# DCDC_Jetson.net
KiCad netlist of a schematic drawn in Altium Designer
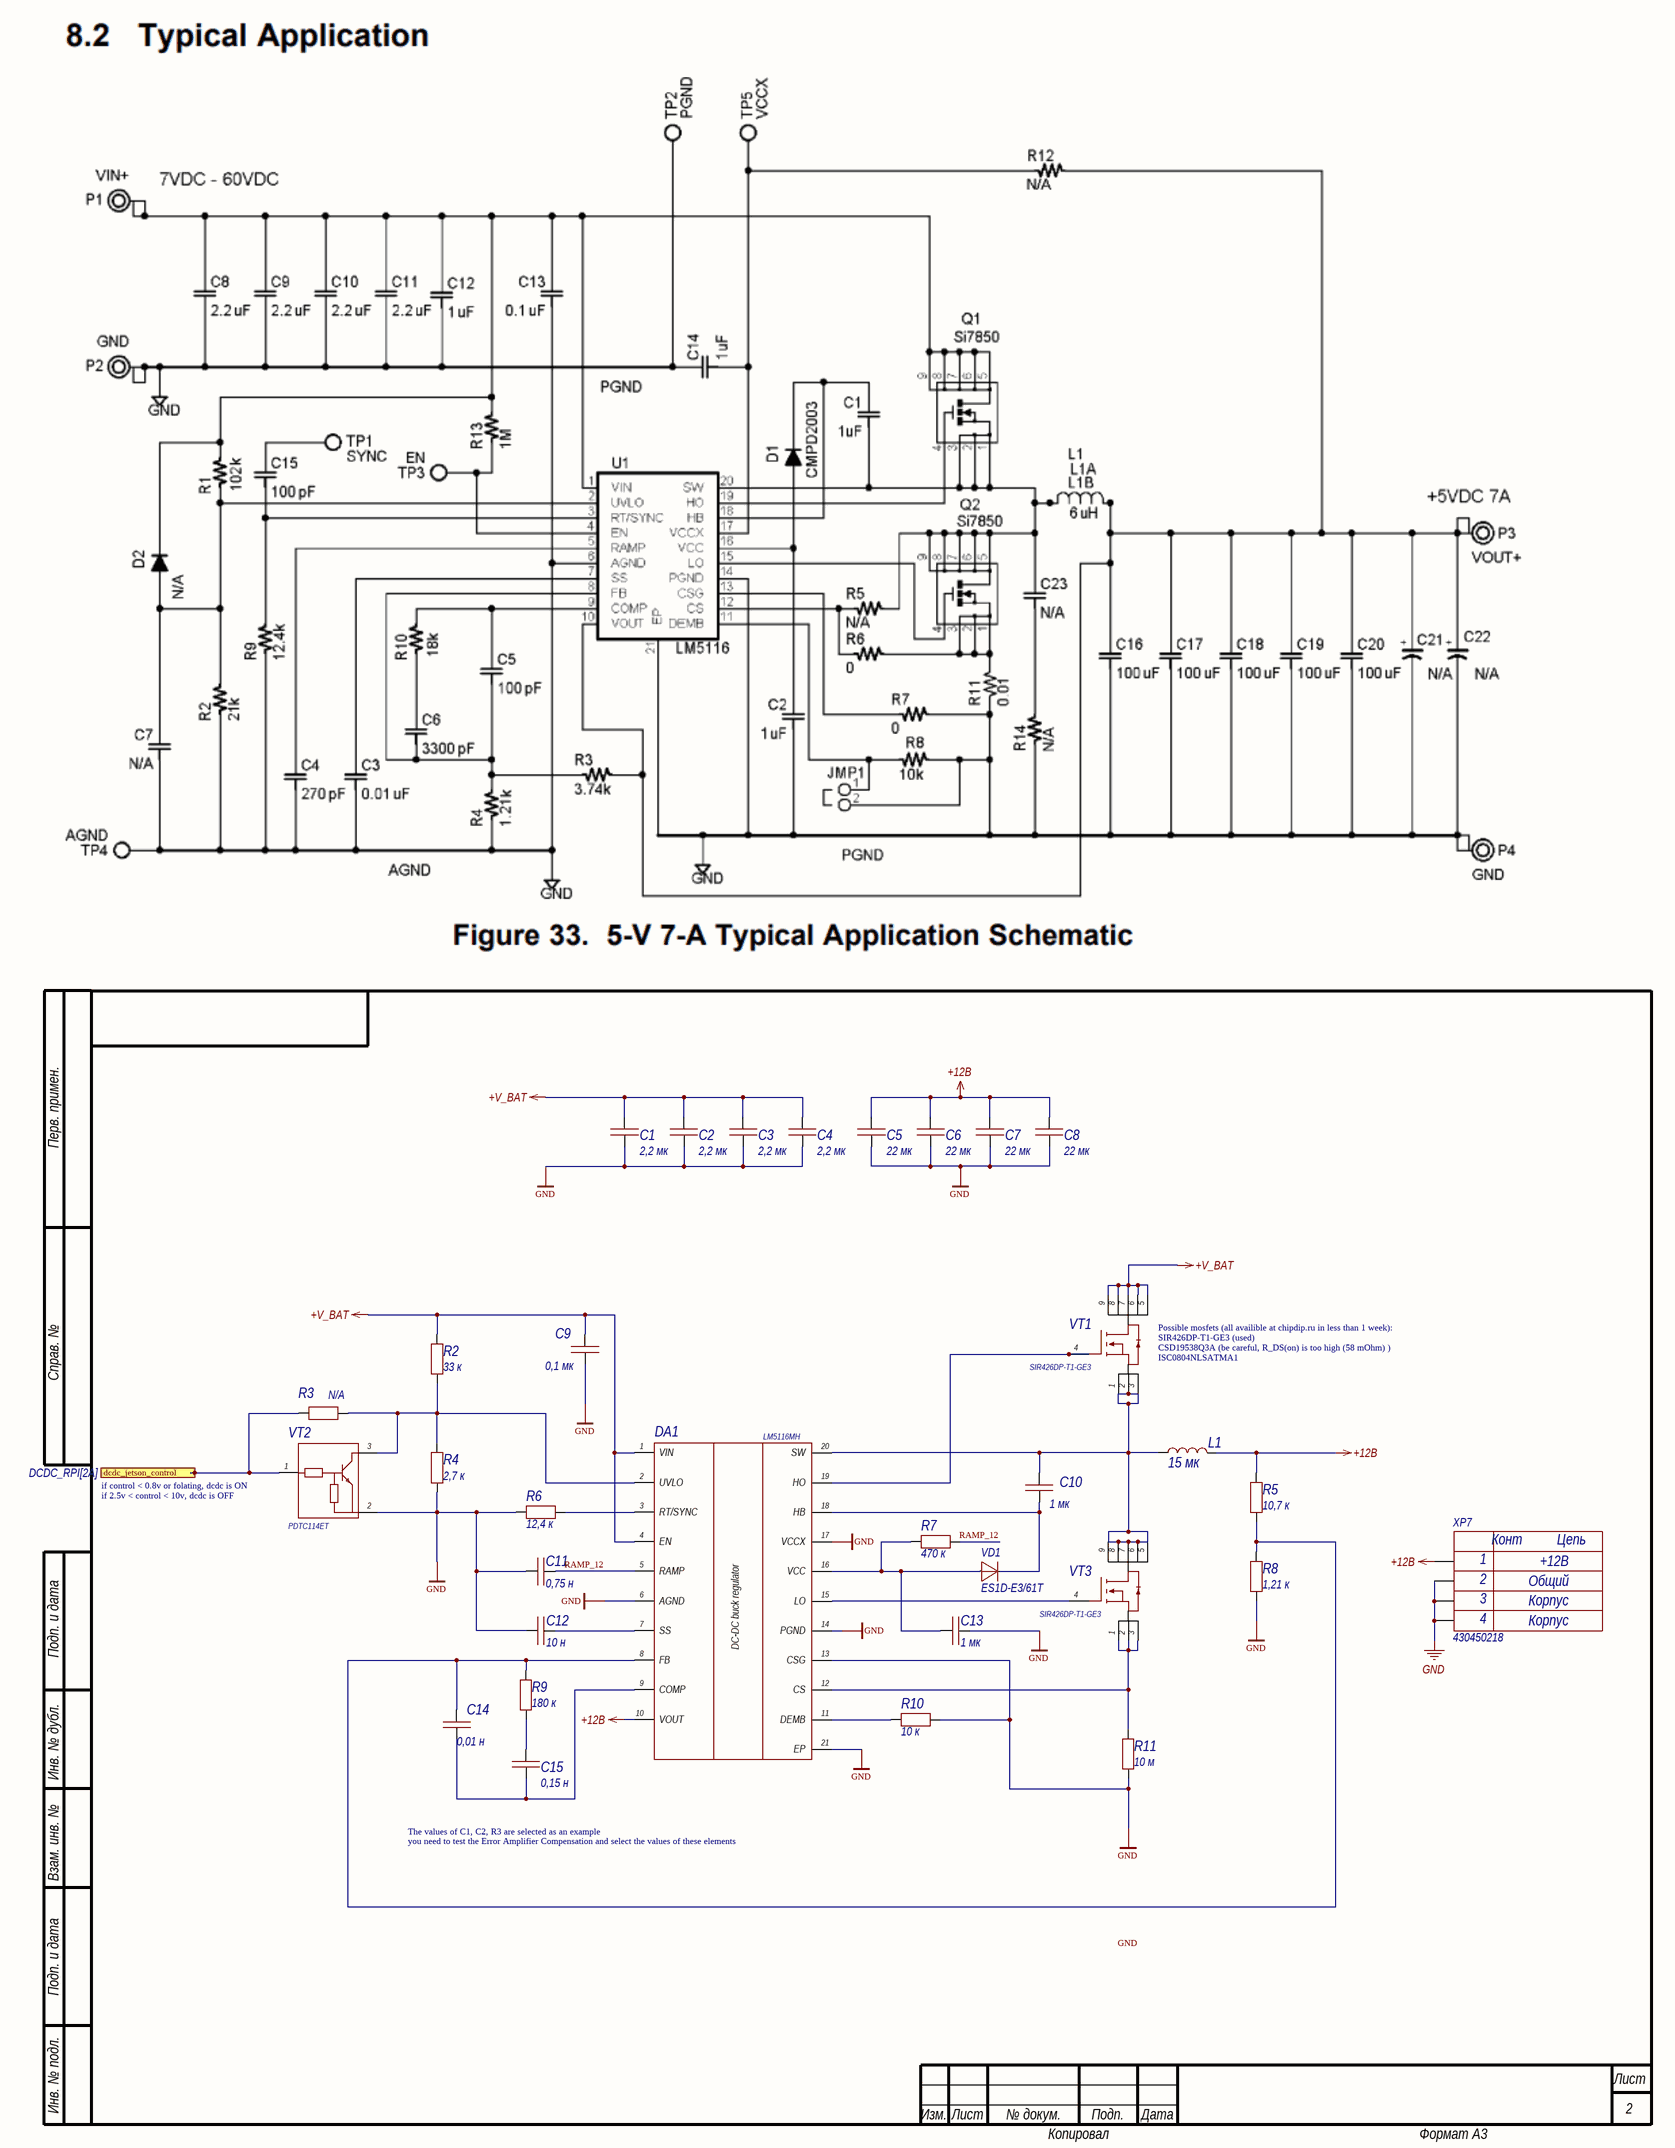
[diagram p0: DCDC_Jetson.SchDoc]

(export (version "E")
  (design (tool "Eeschema 10.0.6"))
  (components
    (comp (ref "C1")
      (value "2,2 мк")
      (footprint "1206C")
      (description "Конденсатор")
      (fields (field (name "PART NUMBER") "Capacitor_2,2u_10_50V_X7R_1206C") (field (name "TOLERANCE") "0,1"))
      (libsource (lib "Hydrolib") (part "Capacitor"))
    )
    (comp (ref "C2")
      (value "2,2 мк")
      (footprint "1206C")
      (description "Конденсатор")
      (fields (field (name "PART NUMBER") "Capacitor_2,2u_10_50V_X7R_1206C") (field (name "TOLERANCE") "0,1"))
      (libsource (lib "Hydrolib") (part "Capacitor"))
    )
    (comp (ref "C3")
      (value "2,2 мк")
      (footprint "1206C")
      (description "Конденсатор")
      (fields (field (name "PART NUMBER") "Capacitor_2,2u_10_50V_X7R_1206C") (field (name "TOLERANCE") "0,1"))
      (libsource (lib "Hydrolib") (part "Capacitor"))
    )
    (comp (ref "C4")
      (value "2,2 мк")
      (footprint "1206C")
      (description "Конденсатор")
      (fields (field (name "PART NUMBER") "Capacitor_2,2u_10_50V_X7R_1206C") (field (name "TOLERANCE") "0,1"))
      (libsource (lib "Hydrolib") (part "Capacitor"))
    )
    (comp (ref "C5")
      (value "22 мк")
      (footprint "1210C")
      (description "Конденсатор")
      (fields (field (name "PART NUMBER") "Capacitor_22u_10_25V_X7R_1210C") (field (name "TOLERANCE") "0,1"))
      (libsource (lib "Hydrolib") (part "Capacitor"))
    )
    (comp (ref "C6")
      (value "22 мк")
      (footprint "1210C")
      (description "Конденсатор")
      (fields (field (name "PART NUMBER") "Capacitor_22u_10_25V_X7R_1210C") (field (name "TOLERANCE") "0,1"))
      (libsource (lib "Hydrolib") (part "Capacitor"))
    )
    (comp (ref "C7")
      (value "22 мк")
      (footprint "1210C")
      (description "Конденсатор")
      (fields (field (name "PART NUMBER") "Capacitor_22u_10_25V_X7R_1210C") (field (name "TOLERANCE") "0,1"))
      (libsource (lib "Hydrolib") (part "Capacitor"))
    )
    (comp (ref "C8")
      (value "22 мк")
      (footprint "1210C")
      (description "Конденсатор")
      (fields (field (name "PART NUMBER") "Capacitor_22u_10_25V_X7R_1210C") (field (name "TOLERANCE") "0,1"))
      (libsource (lib "Hydrolib") (part "Capacitor"))
    )
    (comp (ref "C9")
      (value "0,1 мк")
      (footprint "0603C")
      (description "Конденсатор")
      (fields (field (name "PART NUMBER") "Capacitor_0,1u_10_50V_X7R_0603C") (field (name "TOLERANCE") "0,1"))
      (libsource (lib "Hydrolib") (part "Capacitor"))
    )
    (comp (ref "C10")
      (value "1 мк")
      (footprint "0603C")
      (description "Конденсатор")
      (fields (field (name "PART NUMBER") "Capacitor_1u_10_50V_X7R_0603C") (field (name "TOLERANCE") "0,1"))
      (libsource (lib "Hydrolib") (part "Capacitor"))
    )
    (comp (ref "C11")
      (value "0,75 н")
      (footprint "0603C")
      (description "Конденсатор")
      (fields
        (field (name "PART NUMBER") "Capacitor_0,75n_10_50V_X7R_0603C")
        (field (name "TOLERANCE") "0,1")
      )
      (libsource (lib "Hydrolib") (part "Capacitor"))
    )
    (comp (ref "C12")
      (value "10 н")
      (footprint "0603C")
      (description "Конденсатор")
      (fields (field (name "PART NUMBER") "Capacitor_10n_10_50V_X7R_0603C") (field (name "TOLERANCE") "0,1"))
      (libsource (lib "Hydrolib") (part "Capacitor"))
    )
    (comp (ref "C13")
      (value "1 мк")
      (footprint "0603C")
      (description "Конденсатор")
      (fields (field (name "PART NUMBER") "Capacitor_1u_10_50V_X7R_0603C") (field (name "TOLERANCE") "0,1"))
      (libsource (lib "Hydrolib") (part "Capacitor"))
    )
    (comp (ref "C14")
      (value "0,01 н")
      (footprint "0603C")
      (description "Конденсатор")
      (fields
        (field (name "PART NUMBER") "Capacitor_0,01n_10_50V_X7R_0603C")
        (field (name "TOLERANCE") "0,1")
      )
      (libsource (lib "Hydrolib") (part "Capacitor"))
    )
    (comp (ref "C15")
      (value "0,15 н")
      (footprint "0603C")
      (description "Конденсатор")
      (fields
        (field (name "PART NUMBER") "Capacitor_0,15n_10_50V_X7R_0603C")
        (field (name "TOLERANCE") "0,1")
      )
      (libsource (lib "Hydrolib") (part "Capacitor"))
    )
    (comp (ref "DA1")
      (value "LM5116MH")
      (footprint "HTSSOP-20")
      (description "dc-dc понижающий adj 6-100v")
      (fields (field (name "MANUFACTURER_PART_NUMBER") "LM5116MH/NOPB"))
      (libsource (lib "Hydrolib") (part "LM5116MH"))
    )
    (comp (ref "L1")
      (value "15 мк")
      (footprint "SPRH127")
      (description "Индуктивность на 15 мкГн, номинальный ток 8,4 А")
      (fields (field (name "PART NUMBER") "CDSPRH127-150M"))
      (libsource (lib "Hydrolib") (part "Inductance"))
    )
    (comp (ref "R2")
      (value "33 к")
      (footprint "0603R")
      (description "Резистор номиналом 33 кОм и точностью 1%")
      (fields (field (name "PART NUMBER") "Resistor_33k_1_0603") (field (name "TOLERANCE") "1%"))
      (libsource (lib "") (part "Resistor_1"))
    )
    (comp (ref "R3")
      (value "N/A")
      (footprint "0603R")
      (description "посадочное место 0603 под перемычку")
      (fields (field (name "PART NUMBER") "res_0603_N/A") (field (name "TOLERANCE") "1%"))
      (libsource (lib "Hydrolib") (part "Resistor"))
    )
    (comp (ref "R4")
      (value "2,7 к")
      (footprint "0603R")
      (description "Резистор номиналом 2,7 кОм и точностью 1%")
      (fields (field (name "PART NUMBER") "Resistor_2.7k_1_0603") (field (name "TOLERANCE") "1%"))
      (libsource (lib "") (part "Resistor_1"))
    )
    (comp (ref "R5")
      (value "10,7 к")
      (footprint "0603R")
      (description "Резистор номиналом 10,7 кОм и точностью 1%")
      (fields (field (name "PART NUMBER") "Resistor_10.7k_1_0603") (field (name "TOLERANCE") "1%"))
      (libsource (lib "") (part "Resistor_1"))
    )
    (comp (ref "R6")
      (value "12,4 к")
      (footprint "0603R")
      (description "Резистор номиналом 12,4 кОм и точностью 1%")
      (fields (field (name "PART NUMBER") "Resistor_12.4k_1_0603") (field (name "TOLERANCE") "1%"))
      (libsource (lib "Hydrolib") (part "Resistor"))
    )
    (comp (ref "R7")
      (value "470 к")
      (footprint "0603R")
      (description "Резистор номиналом 470 кОм и точностью 1%")
      (fields (field (name "PART NUMBER") "Resistor_470k_1_0603") (field (name "TOLERANCE") "1%"))
      (libsource (lib "Hydrolib") (part "Resistor"))
    )
    (comp (ref "R8")
      (value "1,21 к")
      (footprint "0603R")
      (description "Резистор номиналом 1,21 кОм и точностью 1%")
      (fields (field (name "PART NUMBER") "Resistor_1.21k_1_0603") (field (name "TOLERANCE") "1%"))
      (libsource (lib "") (part "Resistor_1"))
    )
    (comp (ref "R9")
      (value "180 к")
      (footprint "0603R")
      (description "Резистор номиналом 180 кОм и точностью 1%")
      (fields (field (name "PART NUMBER") "Resistor_180k_1_0603") (field (name "TOLERANCE") "1%"))
      (libsource (lib "") (part "Resistor_1"))
    )
    (comp (ref "R10")
      (value "10 к")
      (footprint "0603R")
      (description "Резистор номиналом 10 кОм и точностью 1%")
      (fields (field (name "PART NUMBER") "Resistor_10k_1_0603") (field (name "TOLERANCE") "1%"))
      (libsource (lib "Hydrolib") (part "Resistor"))
    )
    (comp (ref "R11")
      (value "10 м")
      (footprint "1210R")
      (description "Резистор номиналом 10 мОм, точностью 1%, 0.5Вт")
      (fields (field (name "PART NUMBER") "RL1210FR-070R01L") (field (name "TOLERANCE") "1%"))
      (libsource (lib "") (part "Resistor_1"))
    )
    (comp (ref "VD1")
      (value "ES1D-E3/61T")
      (footprint "SMA")
      (description "Диод 1A 200V")
      (libsource (lib "Hydrolib") (part "Rectifier_diode"))
    )
    (comp (ref "VT1")
      (value "SIR426DP-T1-GE3")
      (footprint "PowerPAK_SO-8")
      (description "Транзистор полевой MOSFET N-канальный 40В 41.7Вт")
      (libsource (lib "Hydrolib") (part "SIR426DP-T1-GE3"))
    )
    (comp (ref "VT2")
      (value "PDTC114ET")
      (footprint "SOT23-3")
      (description "цифровой npn 50в 100мА")
      (libsource (lib "Hydrolib") (part "PDTC114ET"))
    )
    (comp (ref "VT3")
      (value "SIR426DP-T1-GE3")
      (footprint "PowerPAK_SO-8")
      (description "Транзистор полевой MOSFET N-канальный 40В 41.7Вт")
      (libsource (lib "Hydrolib") (part "SIR426DP-T1-GE3"))
    )
    (comp (ref "XP7")
      (value "430450218")
      (footprint "Molex_430450218")
      (fields
        (field (name "VALUE3") "Корпус")
        (field (name "VALUE2") "Общий")
        (field (name "VALUE4") "Корпус")
        (field (name "VALUE1") "+12В")
        (field (name "PART NUMBER") "Molex_430450218")
      )
      (libsource (lib "Hydrolib") (part "Molex_430450218"))
    )
  )
  (nets
    (net (code "1") (name "+12В") (class "Default")
      (node (ref "C5") (pin "2") (pinfunction "2_2") (pintype "passive"))
      (node (ref "C6") (pin "2") (pinfunction "2_2") (pintype "passive"))
      (node (ref "C7") (pin "2") (pinfunction "2_2") (pintype "passive"))
      (node (ref "C8") (pin "2") (pinfunction "2_2") (pintype "passive"))
      (node (ref "DA1") (pin "10") (pinfunction "VOUT_10") (pintype "passive"))
      (node (ref "L1") (pin "2") (pinfunction "2_2") (pintype "passive"))
      (node (ref "R5") (pin "2") (pinfunction "2_2") (pintype "passive"))
      (node (ref "XP7") (pin "1") (pinfunction "1_1") (pintype "passive"))
    )
    (net (code "2") (name "+V_BAT") (class "Default")
      (node (ref "C1") (pin "2") (pinfunction "2_2") (pintype "passive"))
      (node (ref "C2") (pin "2") (pinfunction "2_2") (pintype "passive"))
      (node (ref "C3") (pin "2") (pinfunction "2_2") (pintype "passive"))
      (node (ref "C4") (pin "2") (pinfunction "2_2") (pintype "passive"))
      (node (ref "C9") (pin "2") (pinfunction "2_2") (pintype "passive"))
      (node (ref "DA1") (pin "1") (pinfunction "VIN_1") (pintype "passive"))
      (node (ref "DA1") (pin "4") (pinfunction "EN_4") (pintype "passive"))
      (node (ref "R2") (pin "2") (pinfunction "2_2") (pintype "passive"))
      (node (ref "VT1") (pin "5") (pinfunction "5_5") (pintype "passive"))
      (node (ref "VT1") (pin "6") (pinfunction "6_6") (pintype "passive"))
      (node (ref "VT1") (pin "7") (pinfunction "7_7") (pintype "passive"))
      (node (ref "VT1") (pin "8") (pinfunction "8_8") (pintype "passive"))
      (node (ref "VT1") (pin "9") (pinfunction "9_9") (pintype "passive"))
    )
    (net (code "3") (name "/RAMP_12") (class "Default")
      (node (ref "C11") (pin "2") (pinfunction "2_2") (pintype "passive"))
      (node (ref "DA1") (pin "5") (pinfunction "RAMP_5") (pintype "passive"))
      (node (ref "R7") (pin "2") (pinfunction "2_2") (pintype "passive"))
    )
    (net (code "4") (name "/dcdc_jetson_control") (class "Default")
      (node (ref "R3") (pin "1") (pinfunction "1_1") (pintype "passive"))
      (node (ref "VT2") (pin "1") (pinfunction "B_1") (pintype "passive"))
    )
    (net (code "5") (name "GND") (class "Default")
      (node (ref "C1") (pin "1") (pinfunction "1_1") (pintype "passive"))
      (node (ref "C11") (pin "1") (pinfunction "1_1") (pintype "passive"))
      (node (ref "C12") (pin "1") (pinfunction "1_1") (pintype "passive"))
      (node (ref "C13") (pin "2") (pinfunction "2_2") (pintype "passive"))
      (node (ref "C2") (pin "1") (pinfunction "1_1") (pintype "passive"))
      (node (ref "C3") (pin "1") (pinfunction "1_1") (pintype "passive"))
      (node (ref "C4") (pin "1") (pinfunction "1_1") (pintype "passive"))
      (node (ref "C5") (pin "1") (pinfunction "1_1") (pintype "passive"))
      (node (ref "C6") (pin "1") (pinfunction "1_1") (pintype "passive"))
      (node (ref "C7") (pin "1") (pinfunction "1_1") (pintype "passive"))
      (node (ref "C8") (pin "1") (pinfunction "1_1") (pintype "passive"))
      (node (ref "C9") (pin "1") (pinfunction "1_1") (pintype "passive"))
      (node (ref "DA1") (pin "13") (pinfunction "CSG_13") (pintype "passive"))
      (node (ref "DA1") (pin "14") (pinfunction "PGND_14") (pintype "passive"))
      (node (ref "DA1") (pin "17") (pinfunction "VCCX_17") (pintype "passive"))
      (node (ref "DA1") (pin "21") (pinfunction "EP_21") (pintype "passive"))
      (node (ref "DA1") (pin "6") (pinfunction "AGND_6") (pintype "passive"))
      (node (ref "R10") (pin "2") (pinfunction "2_2") (pintype "passive"))
      (node (ref "R11") (pin "1") (pinfunction "1_1") (pintype "passive"))
      (node (ref "R4") (pin "1") (pinfunction "1_1") (pintype "passive"))
      (node (ref "R6") (pin "1") (pinfunction "1_1") (pintype "passive"))
      (node (ref "R8") (pin "1") (pinfunction "1_1") (pintype "passive"))
      (node (ref "VT2") (pin "2") (pinfunction "E_2") (pintype "passive"))
      (node (ref "XP7") (pin "0") (pinfunction "0_0") (pintype "passive"))
      (node (ref "XP7") (pin "2") (pinfunction "2_2") (pintype "passive"))
    )
    (net (code "6") (name "Net-(C15-Pad2)") (class "Default")
      (node (ref "C15") (pin "2") (pinfunction "2_2") (pintype "passive"))
      (node (ref "R9") (pin "1") (pinfunction "1_1") (pintype "passive"))
    )
    (net (code "7") (name "Net-(DA1-COMP)") (class "Default")
      (node (ref "C14") (pin "1") (pinfunction "1_1") (pintype "passive"))
      (node (ref "C15") (pin "1") (pinfunction "1_1") (pintype "passive"))
      (node (ref "DA1") (pin "9") (pinfunction "COMP_9") (pintype "passive"))
    )
    (net (code "8") (name "Net-(DA1-CS)") (class "Default")
      (node (ref "DA1") (pin "12") (pinfunction "CS_12") (pintype "passive"))
      (node (ref "R11") (pin "2") (pinfunction "2_2") (pintype "passive"))
      (node (ref "VT3") (pin "1") (pinfunction "1_1") (pintype "passive"))
      (node (ref "VT3") (pin "2") (pinfunction "2_2") (pintype "passive"))
      (node (ref "VT3") (pin "3") (pinfunction "3_3") (pintype "passive"))
    )
    (net (code "9") (name "Net-(DA1-DEMB)") (class "Default")
      (node (ref "DA1") (pin "11") (pinfunction "DEMB_11") (pintype "passive"))
      (node (ref "R10") (pin "1") (pinfunction "1_1") (pintype "passive"))
    )
    (net (code "10") (name "Net-(DA1-FB)") (class "Default")
      (node (ref "C14") (pin "2") (pinfunction "2_2") (pintype "passive"))
      (node (ref "DA1") (pin "8") (pinfunction "FB_8") (pintype "passive"))
      (node (ref "R5") (pin "1") (pinfunction "1_1") (pintype "passive"))
      (node (ref "R8") (pin "2") (pinfunction "2_2") (pintype "passive"))
      (node (ref "R9") (pin "2") (pinfunction "2_2") (pintype "passive"))
    )
    (net (code "11") (name "Net-(DA1-HB)") (class "Default")
      (node (ref "C10") (pin "1") (pinfunction "1_1") (pintype "passive"))
      (node (ref "DA1") (pin "18") (pinfunction "HB_18") (pintype "passive"))
      (node (ref "VD1") (pin "2") (pinfunction "2_2") (pintype "passive"))
    )
    (net (code "12") (name "Net-(DA1-HO)") (class "Default")
      (node (ref "DA1") (pin "19") (pinfunction "HO_19") (pintype "passive"))
      (node (ref "VT1") (pin "4") (pinfunction "4_4") (pintype "passive"))
    )
    (net (code "13") (name "Net-(DA1-LO)") (class "Default")
      (node (ref "DA1") (pin "15") (pinfunction "LO_15") (pintype "passive"))
      (node (ref "VT3") (pin "4") (pinfunction "4_4") (pintype "passive"))
    )
    (net (code "14") (name "Net-(DA1-RT{slash}SYNC)") (class "Default")
      (node (ref "DA1") (pin "3") (pinfunction "RT/SYNC_3") (pintype "passive"))
      (node (ref "R6") (pin "2") (pinfunction "2_2") (pintype "passive"))
    )
    (net (code "15") (name "Net-(DA1-SS)") (class "Default")
      (node (ref "C12") (pin "2") (pinfunction "2_2") (pintype "passive"))
      (node (ref "DA1") (pin "7") (pinfunction "SS_7") (pintype "passive"))
    )
    (net (code "16") (name "Net-(DA1-SW)") (class "Default")
      (node (ref "C10") (pin "2") (pinfunction "2_2") (pintype "passive"))
      (node (ref "DA1") (pin "20") (pinfunction "SW_20") (pintype "passive"))
      (node (ref "L1") (pin "1") (pinfunction "1_1") (pintype "passive"))
      (node (ref "VT1") (pin "1") (pinfunction "1_1") (pintype "passive"))
      (node (ref "VT1") (pin "2") (pinfunction "2_2") (pintype "passive"))
      (node (ref "VT1") (pin "3") (pinfunction "3_3") (pintype "passive"))
      (node (ref "VT3") (pin "5") (pinfunction "5_5") (pintype "passive"))
      (node (ref "VT3") (pin "6") (pinfunction "6_6") (pintype "passive"))
      (node (ref "VT3") (pin "7") (pinfunction "7_7") (pintype "passive"))
      (node (ref "VT3") (pin "8") (pinfunction "8_8") (pintype "passive"))
      (node (ref "VT3") (pin "9") (pinfunction "9_9") (pintype "passive"))
    )
    (net (code "17") (name "Net-(DA1-UVLO)") (class "Default")
      (node (ref "DA1") (pin "2") (pinfunction "UVLO_2") (pintype "passive"))
      (node (ref "R2") (pin "1") (pinfunction "1_1") (pintype "passive"))
      (node (ref "R3") (pin "2") (pinfunction "2_2") (pintype "passive"))
      (node (ref "R4") (pin "2") (pinfunction "2_2") (pintype "passive"))
      (node (ref "VT2") (pin "3") (pinfunction "C_3") (pintype "passive"))
    )
    (net (code "18") (name "Net-(DA1-VCC)") (class "Default")
      (node (ref "C13") (pin "1") (pinfunction "1_1") (pintype "passive"))
      (node (ref "DA1") (pin "16") (pinfunction "VCC_16") (pintype "passive"))
      (node (ref "R7") (pin "1") (pinfunction "1_1") (pintype "passive"))
      (node (ref "VD1") (pin "1") (pinfunction "1_1") (pintype "passive"))
    )
  )
)
